# MotherBoard_PowerSupply_ebay.net
KiCad netlist of a schematic drawn in Altium Designer
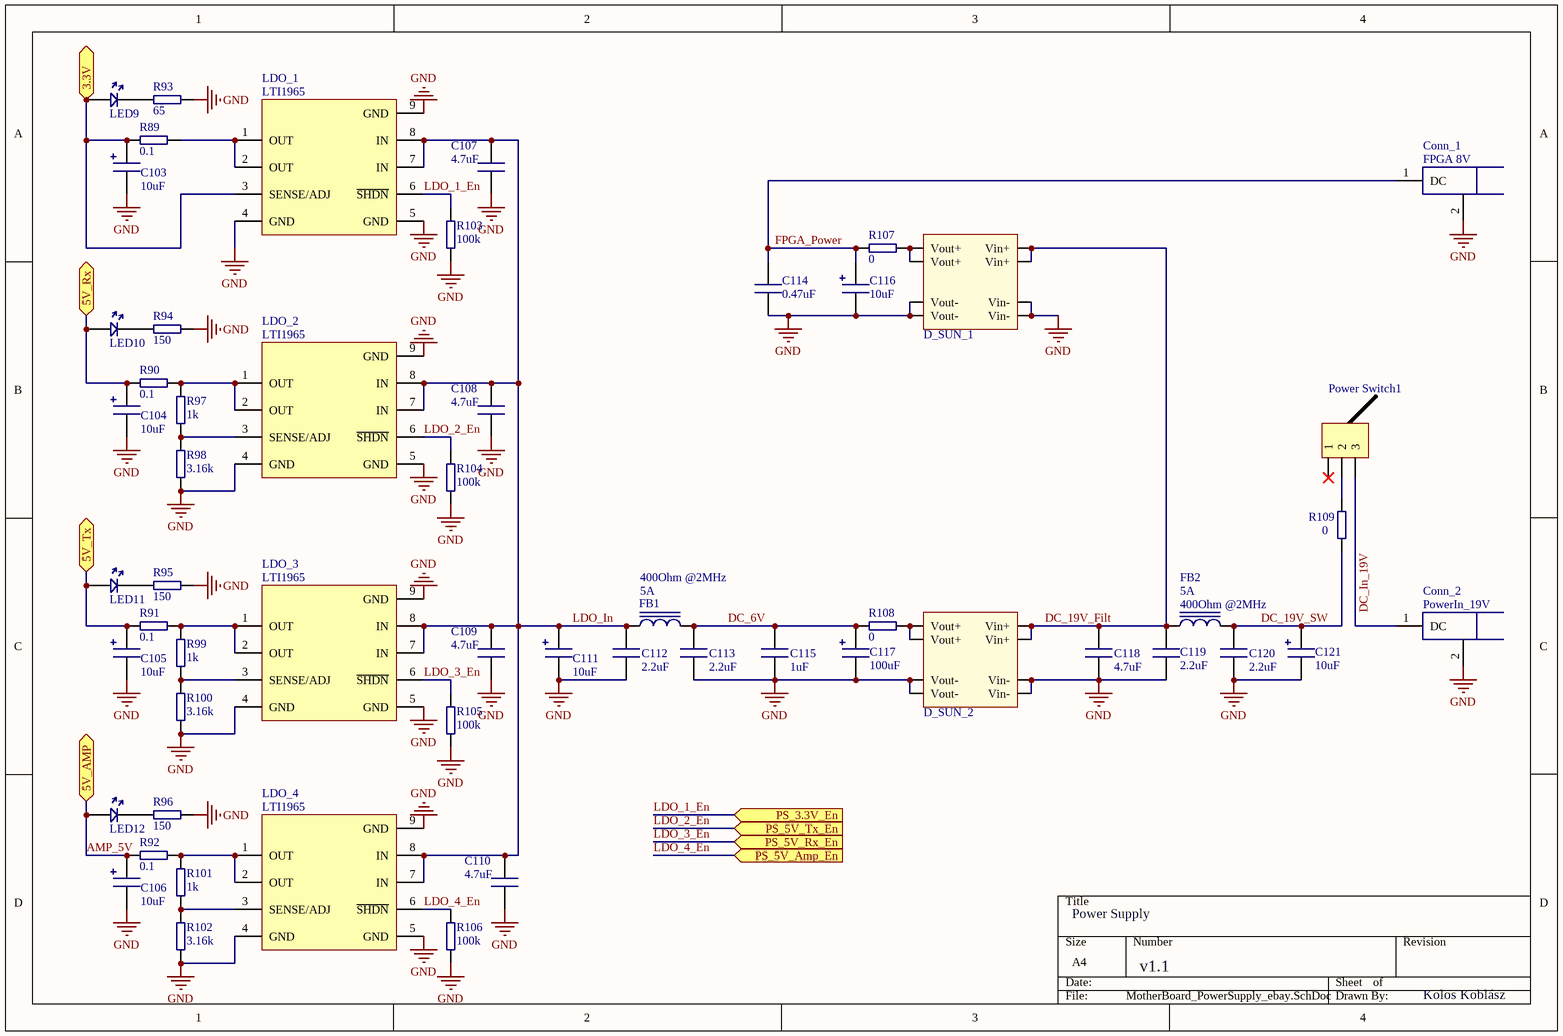
[diagram p0: MotherBoard_PowerSupply_ebay.SchDoc]

(export (version "E")
  (design (tool "Eeschema 10.0.6"))
  (components
    (comp (ref "C103")
      (value "10uF")
      (footprint "ELKO_CAP")
      (description "SMD Polarized Capacitor")
      (fields (field (name "Comment") "Cap2"))
      (libsource (lib "RadioProjectSchLib") (part "Cap2"))
    )
    (comp (ref "C104")
      (value "10uF")
      (footprint "ELKO_CAP")
      (description "SMD Polarized Capacitor")
      (fields (field (name "Comment") "Cap2"))
      (libsource (lib "RadioProjectSchLib") (part "Cap2"))
    )
    (comp (ref "C105")
      (value "10uF")
      (footprint "ELKO_CAP")
      (description "SMD Polarized Capacitor")
      (fields (field (name "Comment") "Cap2"))
      (libsource (lib "RadioProjectSchLib") (part "Cap2"))
    )
    (comp (ref "C106")
      (value "10uF")
      (footprint "ELKO_CAP")
      (description "SMD Polarized Capacitor")
      (fields (field (name "Comment") "Cap2"))
      (libsource (lib "RadioProjectSchLib") (part "Cap2"))
    )
    (comp (ref "C107")
      (value "4.7uF")
      (footprint "0805 SMD Passive")
      (description "SMD Capacitor")
      (fields (field (name "Comment") "Cap1"))
      (libsource (lib "RadioProjectSchLib") (part "Cap1"))
    )
    (comp (ref "C108")
      (value "4.7uF")
      (footprint "0805 SMD Passive")
      (description "SMD Capacitor")
      (fields (field (name "Comment") "Cap1"))
      (libsource (lib "RadioProjectSchLib") (part "Cap1"))
    )
    (comp (ref "C109")
      (value "4.7uF")
      (footprint "0805 SMD Passive")
      (description "SMD Capacitor")
      (fields (field (name "Comment") "Cap1"))
      (libsource (lib "RadioProjectSchLib") (part "Cap1"))
    )
    (comp (ref "C110")
      (value "4.7uF")
      (footprint "0805 SMD Passive")
      (description "SMD Capacitor")
      (fields (field (name "Comment") "Cap1"))
      (libsource (lib "RadioProjectSchLib") (part "Cap1"))
    )
    (comp (ref "C111")
      (value "10uF")
      (footprint "ELKO_CAP")
      (description "SMD Polarized Capacitor")
      (fields (field (name "Comment") "Cap2"))
      (libsource (lib "RadioProjectSchLib") (part "Cap2"))
    )
    (comp (ref "C112")
      (value "2.2uF")
      (footprint "0805 SMD Passive")
      (description "SMD Capacitor")
      (fields (field (name "Comment") "Cap1"))
      (libsource (lib "RadioProjectSchLib") (part "Cap1"))
    )
    (comp (ref "C113")
      (value "2.2uF")
      (footprint "0805 SMD Passive")
      (description "SMD Capacitor")
      (fields (field (name "Comment") "Cap1"))
      (libsource (lib "RadioProjectSchLib") (part "Cap1"))
    )
    (comp (ref "C114")
      (value "0.47uF")
      (footprint "0805 SMD Passive")
      (description "SMD Capacitor")
      (fields (field (name "Comment") "Cap1"))
      (libsource (lib "RadioProjectSchLib") (part "Cap1"))
    )
    (comp (ref "C115")
      (value "1uF")
      (footprint "0805 SMD Passive")
      (description "SMD Capacitor")
      (fields (field (name "Comment") "Cap1"))
      (libsource (lib "RadioProjectSchLib") (part "Cap1"))
    )
    (comp (ref "C116")
      (value "10uF")
      (footprint "ELKO_CAP")
      (description "SMD Polarized Capacitor")
      (fields (field (name "Comment") "Cap2"))
      (libsource (lib "RadioProjectSchLib") (part "Cap2"))
    )
    (comp (ref "C117")
      (value "100uF")
      (footprint "ELKO_CAP")
      (description "SMD Polarized Capacitor")
      (fields (field (name "Comment") "Cap2"))
      (libsource (lib "RadioProjectSchLib") (part "Cap2"))
    )
    (comp (ref "C118")
      (value "4.7uF")
      (footprint "0805 SMD Passive")
      (description "SMD Capacitor")
      (fields (field (name "Comment") "Cap1"))
      (libsource (lib "RadioProjectSchLib") (part "Cap1"))
    )
    (comp (ref "C119")
      (value "2.2uF")
      (footprint "0805 SMD Passive")
      (description "SMD Capacitor")
      (fields (field (name "Comment") "Cap1"))
      (libsource (lib "RadioProjectSchLib") (part "Cap1"))
    )
    (comp (ref "C120")
      (value "2.2uF")
      (footprint "0805 SMD Passive")
      (description "SMD Capacitor")
      (fields (field (name "Comment") "Cap1"))
      (libsource (lib "RadioProjectSchLib") (part "Cap1"))
    )
    (comp (ref "C121")
      (value "10uF")
      (footprint "ELKO_CAP")
      (description "SMD Polarized Capacitor")
      (fields (field (name "Comment") "Cap2"))
      (libsource (lib "RadioProjectSchLib") (part "Cap2"))
    )
    (comp (ref "Conn_1")
      (value "FPGA 8V")
      (footprint "DC_Connector")
      (description "Coaxial DC connector - female")
      (libsource (lib "RadioProjectSchLib") (part "DC_Connector"))
    )
    (comp (ref "Conn_2")
      (value "PowerIn_19V")
      (footprint "DC_Connector")
      (description "Coaxial DC connector - female")
      (libsource (lib "RadioProjectSchLib") (part "DC_Connector"))
    )
    (comp (ref "D_SUN_1")
      (value "D_SUN")
      (footprint "D_SUN")
      (description "3A DC Buck Step down Adjustable Converter Module 5-28V to 3-20V")
      (fields (field (name "MANUFACTURER") "elec modul 58"))
      (libsource (lib "RadioProjectSchLib") (part "D_SUN"))
    )
    (comp (ref "D_SUN_2")
      (value "D_SUN")
      (footprint "D_SUN")
      (description "3A DC Buck Step down Adjustable Converter Module 5-28V to 3-20V")
      (fields (field (name "MANUFACTURER") "elec modul 58"))
      (libsource (lib "RadioProjectSchLib") (part "D_SUN"))
    )
    (comp (ref "FB1")
      (value "400Ohm @2MHz")
      (footprint "FerritBead")
      (description "Ferrit Bead")
      (fields (field (name "MAXCURENT") "5A") (field (name "PARTNUMBER") "FB20022-4B-RC"))
      (libsource (lib "RadioProjectSchLib") (part "FerritBead"))
    )
    (comp (ref "FB2")
      (value "400Ohm @2MHz")
      (footprint "FerritBead")
      (description "Ferrit Bead")
      (fields (field (name "MAXCURENT") "5A") (field (name "PARTNUMBER") "FB20022-4B-RC"))
      (libsource (lib "RadioProjectSchLib") (part "FerritBead"))
    )
    (comp (ref "LDO_1")
      (value "LTI1965")
      (footprint "LT1965")
      (description "Low Dropout Linear Regulator")
      (fields (field (name "MANUFACTURER") "Analog Devices"))
      (libsource (lib "RadioProjectSchLib") (part "LTI1965"))
    )
    (comp (ref "LDO_2")
      (value "LTI1965")
      (footprint "LT1965")
      (description "Low Dropout Linear Regulator")
      (fields (field (name "MANUFACTURER") "Analog Devices"))
      (libsource (lib "RadioProjectSchLib") (part "LTI1965"))
    )
    (comp (ref "LDO_3")
      (value "LTI1965")
      (footprint "LT1965")
      (description "Low Dropout Linear Regulator")
      (fields (field (name "MANUFACTURER") "Analog Devices"))
      (libsource (lib "RadioProjectSchLib") (part "LTI1965"))
    )
    (comp (ref "LDO_4")
      (value "LTI1965")
      (footprint "LT1965")
      (description "Low Dropout Linear Regulator")
      (fields (field (name "MANUFACTURER") "Analog Devices"))
      (libsource (lib "RadioProjectSchLib") (part "LTI1965"))
    )
    (comp (ref "LED9")
      (value "LED_Green")
      (footprint "0805 SMD Passive")
      (description "Diode")
      (fields (field (name "MANUFACTURER") "LITEON") (field (name "PARTNUMBER") "LTST-C171KGKT"))
      (libsource (lib "RadioProjectSchLib") (part "LED_Green"))
    )
    (comp (ref "LED10")
      (value "LED_Green")
      (footprint "0805 SMD Passive")
      (description "Diode")
      (fields (field (name "MANUFACTURER") "LITEON") (field (name "PARTNUMBER") "LTST-C171KGKT"))
      (libsource (lib "RadioProjectSchLib") (part "LED_Green"))
    )
    (comp (ref "LED11")
      (value "LED_Green")
      (footprint "0805 SMD Passive")
      (description "Diode")
      (fields (field (name "MANUFACTURER") "LITEON") (field (name "PARTNUMBER") "LTST-C171KGKT"))
      (libsource (lib "RadioProjectSchLib") (part "LED_Green"))
    )
    (comp (ref "LED12")
      (value "LED_Green")
      (footprint "0805 SMD Passive")
      (description "Diode")
      (fields (field (name "MANUFACTURER") "LITEON") (field (name "PARTNUMBER") "LTST-C171KGKT"))
      (libsource (lib "RadioProjectSchLib") (part "LED_Green"))
    )
    (comp (ref "Power Switch1")
      (value "Switch")
      (footprint "Switch")
      (description "3 state switch")
      (libsource (lib "RadioProjectSchLib") (part "Switch"))
    )
    (comp (ref "R89")
      (value "0.1")
      (footprint "0805 SMD Passive")
      (description "SMD Resistor")
      (fields (field (name "Comment") "Resistor"))
      (libsource (lib "RadioProjectSchLib") (part "Res1"))
    )
    (comp (ref "R90")
      (value "0.1")
      (footprint "0805 SMD Passive")
      (description "SMD Resistor")
      (fields (field (name "Comment") "Resistor"))
      (libsource (lib "RadioProjectSchLib") (part "Res1"))
    )
    (comp (ref "R91")
      (value "0.1")
      (footprint "0805 SMD Passive")
      (description "SMD Resistor")
      (fields (field (name "Comment") "Resistor"))
      (libsource (lib "RadioProjectSchLib") (part "Res1"))
    )
    (comp (ref "R92")
      (value "0.1")
      (footprint "0805 SMD Passive")
      (description "SMD Resistor")
      (fields (field (name "Comment") "Resistor"))
      (libsource (lib "RadioProjectSchLib") (part "Res1"))
    )
    (comp (ref "R93")
      (value "65")
      (footprint "0805 SMD Passive")
      (description "SMD Resistor")
      (fields (field (name "Comment") "Resistor"))
      (libsource (lib "RadioProjectSchLib") (part "Res1"))
    )
    (comp (ref "R94")
      (value "150")
      (footprint "0805 SMD Passive")
      (description "SMD Resistor")
      (fields (field (name "Comment") "Resistor"))
      (libsource (lib "RadioProjectSchLib") (part "Res1"))
    )
    (comp (ref "R95")
      (value "150")
      (footprint "0805 SMD Passive")
      (description "SMD Resistor")
      (fields (field (name "Comment") "Resistor"))
      (libsource (lib "RadioProjectSchLib") (part "Res1"))
    )
    (comp (ref "R96")
      (value "150")
      (footprint "0805 SMD Passive")
      (description "SMD Resistor")
      (fields (field (name "Comment") "Resistor"))
      (libsource (lib "RadioProjectSchLib") (part "Res1"))
    )
    (comp (ref "R97")
      (value "1k")
      (footprint "0805 SMD Passive")
      (description "SMD Resistor")
      (fields (field (name "Comment") "Resistor"))
      (libsource (lib "RadioProjectSchLib") (part "Res1"))
    )
    (comp (ref "R98")
      (value "3.16k")
      (footprint "0805 SMD Passive")
      (description "SMD Resistor")
      (fields (field (name "Comment") "Resistor"))
      (libsource (lib "RadioProjectSchLib") (part "Res1"))
    )
    (comp (ref "R99")
      (value "1k")
      (footprint "0805 SMD Passive")
      (description "SMD Resistor")
      (fields (field (name "Comment") "Resistor"))
      (libsource (lib "RadioProjectSchLib") (part "Res1"))
    )
    (comp (ref "R100")
      (value "3.16k")
      (footprint "0805 SMD Passive")
      (description "SMD Resistor")
      (fields (field (name "Comment") "Resistor"))
      (libsource (lib "RadioProjectSchLib") (part "Res1"))
    )
    (comp (ref "R101")
      (value "1k")
      (footprint "0805 SMD Passive")
      (description "SMD Resistor")
      (fields (field (name "Comment") "Resistor"))
      (libsource (lib "RadioProjectSchLib") (part "Res1"))
    )
    (comp (ref "R102")
      (value "3.16k")
      (footprint "0805 SMD Passive")
      (description "SMD Resistor")
      (fields (field (name "Comment") "Resistor"))
      (libsource (lib "RadioProjectSchLib") (part "Res1"))
    )
    (comp (ref "R103")
      (value "100k")
      (footprint "0805 SMD Passive")
      (description "SMD Resistor")
      (fields (field (name "Comment") "Resistor"))
      (libsource (lib "RadioProjectSchLib") (part "Res1"))
    )
    (comp (ref "R104")
      (value "100k")
      (footprint "0805 SMD Passive")
      (description "SMD Resistor")
      (fields (field (name "Comment") "Resistor"))
      (libsource (lib "RadioProjectSchLib") (part "Res1"))
    )
    (comp (ref "R105")
      (value "100k")
      (footprint "0805 SMD Passive")
      (description "SMD Resistor")
      (fields (field (name "Comment") "Resistor"))
      (libsource (lib "RadioProjectSchLib") (part "Res1"))
    )
    (comp (ref "R106")
      (value "100k")
      (footprint "0805 SMD Passive")
      (description "SMD Resistor")
      (fields (field (name "Comment") "Resistor"))
      (libsource (lib "RadioProjectSchLib") (part "Res1"))
    )
    (comp (ref "R107")
      (value "0")
      (footprint "0805 SMD Passive")
      (description "SMD Resistor")
      (fields (field (name "Comment") "Resistor"))
      (libsource (lib "RadioProjectSchLib") (part "Res1"))
    )
    (comp (ref "R108")
      (value "0")
      (footprint "0805 SMD Passive")
      (description "SMD Resistor")
      (fields (field (name "Comment") "Resistor"))
      (libsource (lib "RadioProjectSchLib") (part "Res1"))
    )
    (comp (ref "R109")
      (value "0")
      (footprint "0805 SMD Passive")
      (description "SMD Resistor")
      (fields (field (name "Comment") "Resistor"))
      (libsource (lib "RadioProjectSchLib") (part "Res1"))
    )
  )
  (nets
    (net (code "1") (name "/3.3V") (class "Default")
      (node (ref "C103") (pin "1") (pinfunction "*_1") (pintype "passive"))
      (node (ref "LDO_1") (pin "3") (pinfunction "SENSE/ADJ_3") (pintype "passive"))
      (node (ref "LED9") (pin "2") (pinfunction "A_2") (pintype "passive"))
      (node (ref "R89") (pin "1") (pinfunction "*_1") (pintype "passive"))
    )
    (net (code "2") (name "/5V_Rx") (class "Default")
      (node (ref "C104") (pin "1") (pinfunction "*_1") (pintype "passive"))
      (node (ref "LED10") (pin "2") (pinfunction "A_2") (pintype "passive"))
      (node (ref "R90") (pin "1") (pinfunction "*_1") (pintype "passive"))
    )
    (net (code "3") (name "/5V_Tx") (class "Default")
      (node (ref "C105") (pin "1") (pinfunction "*_1") (pintype "passive"))
      (node (ref "LED11") (pin "2") (pinfunction "A_2") (pintype "passive"))
      (node (ref "R91") (pin "1") (pinfunction "*_1") (pintype "passive"))
    )
    (net (code "4") (name "/AMP_5V") (class "Default")
      (node (ref "C106") (pin "1") (pinfunction "*_1") (pintype "passive"))
      (node (ref "LED12") (pin "2") (pinfunction "A_2") (pintype "passive"))
      (node (ref "R92") (pin "1") (pinfunction "*_1") (pintype "passive"))
    )
    (net (code "5") (name "/DC_6V") (class "Default")
      (node (ref "C113") (pin "2") (pinfunction "*_2") (pintype "passive"))
      (node (ref "C115") (pin "1") (pinfunction "*_1") (pintype "passive"))
      (node (ref "C117") (pin "1") (pinfunction "*_1") (pintype "passive"))
      (node (ref "FB1") (pin "2") (pinfunction "*_2") (pintype "passive"))
      (node (ref "R108") (pin "2") (pinfunction "*_2") (pintype "passive"))
    )
    (net (code "6") (name "/DC_19V_Filt") (class "Default")
      (node (ref "C118") (pin "2") (pinfunction "*_2") (pintype "passive"))
      (node (ref "C119") (pin "2") (pinfunction "*_2") (pintype "passive"))
      (node (ref "D_SUN_1") (pin "3") (pinfunction "Vin+_3") (pintype "passive"))
      (node (ref "D_SUN_1") (pin "4") (pinfunction "Vin+_4") (pintype "passive"))
      (node (ref "D_SUN_2") (pin "3") (pinfunction "Vin+_3") (pintype "passive"))
      (node (ref "D_SUN_2") (pin "4") (pinfunction "Vin+_4") (pintype "passive"))
      (node (ref "FB2") (pin "1") (pinfunction "*_1") (pintype "passive"))
    )
    (net (code "7") (name "/DC_19V_SW") (class "Default")
      (node (ref "C120") (pin "2") (pinfunction "*_2") (pintype "passive"))
      (node (ref "C121") (pin "1") (pinfunction "*_1") (pintype "passive"))
      (node (ref "FB2") (pin "2") (pinfunction "*_2") (pintype "passive"))
      (node (ref "R109") (pin "2") (pinfunction "*_2") (pintype "passive"))
    )
    (net (code "8") (name "/DC_In_19V") (class "Default")
      (node (ref "Conn_2") (pin "1") (pinfunction "DC_1") (pintype "passive"))
      (node (ref "Power Switch1") (pin "3") (pinfunction "3_3") (pintype "passive"))
    )
    (net (code "9") (name "/FPGA_Power") (class "Default")
      (node (ref "C114") (pin "2") (pinfunction "*_2") (pintype "passive"))
      (node (ref "C116") (pin "1") (pinfunction "*_1") (pintype "passive"))
      (node (ref "Conn_1") (pin "1") (pinfunction "DC_1") (pintype "passive"))
      (node (ref "R107") (pin "2") (pinfunction "*_2") (pintype "passive"))
    )
    (net (code "10") (name "/LDO_1_En") (class "Default")
      (node (ref "LDO_1") (pin "6") (pinfunction "~{SHDN}_6") (pintype "passive"))
      (node (ref "R103") (pin "2") (pinfunction "*_2") (pintype "passive"))
    )
    (net (code "11") (name "/LDO_2_En") (class "Default")
      (node (ref "LDO_2") (pin "6") (pinfunction "~{SHDN}_6") (pintype "passive"))
      (node (ref "R104") (pin "2") (pinfunction "*_2") (pintype "passive"))
    )
    (net (code "12") (name "/LDO_3_En") (class "Default")
      (node (ref "LDO_3") (pin "6") (pinfunction "~{SHDN}_6") (pintype "passive"))
      (node (ref "R105") (pin "2") (pinfunction "*_2") (pintype "passive"))
    )
    (net (code "13") (name "/LDO_4_En") (class "Default")
      (node (ref "LDO_4") (pin "6") (pinfunction "~{SHDN}_6") (pintype "passive"))
      (node (ref "R106") (pin "2") (pinfunction "*_2") (pintype "passive"))
    )
    (net (code "14") (name "/LDO_In") (class "Default")
      (node (ref "C107") (pin "2") (pinfunction "*_2") (pintype "passive"))
      (node (ref "C108") (pin "2") (pinfunction "*_2") (pintype "passive"))
      (node (ref "C109") (pin "2") (pinfunction "*_2") (pintype "passive"))
      (node (ref "C110") (pin "2") (pinfunction "*_2") (pintype "passive"))
      (node (ref "C111") (pin "1") (pinfunction "*_1") (pintype "passive"))
      (node (ref "C112") (pin "2") (pinfunction "*_2") (pintype "passive"))
      (node (ref "FB1") (pin "1") (pinfunction "*_1") (pintype "passive"))
      (node (ref "LDO_1") (pin "7") (pinfunction "IN_7") (pintype "passive"))
      (node (ref "LDO_1") (pin "8") (pinfunction "IN_8") (pintype "passive"))
      (node (ref "LDO_2") (pin "7") (pinfunction "IN_7") (pintype "passive"))
      (node (ref "LDO_2") (pin "8") (pinfunction "IN_8") (pintype "passive"))
      (node (ref "LDO_3") (pin "7") (pinfunction "IN_7") (pintype "passive"))
      (node (ref "LDO_3") (pin "8") (pinfunction "IN_8") (pintype "passive"))
      (node (ref "LDO_4") (pin "7") (pinfunction "IN_7") (pintype "passive"))
      (node (ref "LDO_4") (pin "8") (pinfunction "IN_8") (pintype "passive"))
    )
    (net (code "15") (name "GND") (class "Default")
      (node (ref "C103") (pin "2") (pinfunction "*_2") (pintype "passive"))
      (node (ref "C104") (pin "2") (pinfunction "*_2") (pintype "passive"))
      (node (ref "C105") (pin "2") (pinfunction "*_2") (pintype "passive"))
      (node (ref "C106") (pin "2") (pinfunction "*_2") (pintype "passive"))
      (node (ref "C107") (pin "1") (pinfunction "*_1") (pintype "passive"))
      (node (ref "C108") (pin "1") (pinfunction "*_1") (pintype "passive"))
      (node (ref "C109") (pin "1") (pinfunction "*_1") (pintype "passive"))
      (node (ref "C110") (pin "1") (pinfunction "*_1") (pintype "passive"))
      (node (ref "C111") (pin "2") (pinfunction "*_2") (pintype "passive"))
      (node (ref "C112") (pin "1") (pinfunction "*_1") (pintype "passive"))
      (node (ref "C113") (pin "1") (pinfunction "*_1") (pintype "passive"))
      (node (ref "C114") (pin "1") (pinfunction "*_1") (pintype "passive"))
      (node (ref "C115") (pin "2") (pinfunction "*_2") (pintype "passive"))
      (node (ref "C116") (pin "2") (pinfunction "*_2") (pintype "passive"))
      (node (ref "C117") (pin "2") (pinfunction "*_2") (pintype "passive"))
      (node (ref "C118") (pin "1") (pinfunction "*_1") (pintype "passive"))
      (node (ref "C119") (pin "1") (pinfunction "*_1") (pintype "passive"))
      (node (ref "C120") (pin "1") (pinfunction "*_1") (pintype "passive"))
      (node (ref "C121") (pin "2") (pinfunction "*_2") (pintype "passive"))
      (node (ref "Conn_1") (pin "2") (pinfunction "GND_2") (pintype "passive"))
      (node (ref "Conn_2") (pin "2") (pinfunction "GND_2") (pintype "passive"))
      (node (ref "D_SUN_1") (pin "1") (pinfunction "Vin-_1") (pintype "passive"))
      (node (ref "D_SUN_1") (pin "2") (pinfunction "Vin-_2") (pintype "passive"))
      (node (ref "D_SUN_1") (pin "7") (pinfunction "Vout-_7") (pintype "passive"))
      (node (ref "D_SUN_1") (pin "8") (pinfunction "Vout-_8") (pintype "passive"))
      (node (ref "D_SUN_2") (pin "1") (pinfunction "Vin-_1") (pintype "passive"))
      (node (ref "D_SUN_2") (pin "2") (pinfunction "Vin-_2") (pintype "passive"))
      (node (ref "D_SUN_2") (pin "7") (pinfunction "Vout-_7") (pintype "passive"))
      (node (ref "D_SUN_2") (pin "8") (pinfunction "Vout-_8") (pintype "passive"))
      (node (ref "LDO_1") (pin "4") (pinfunction "GND_4") (pintype "passive"))
      (node (ref "LDO_1") (pin "5") (pinfunction "GND_5") (pintype "passive"))
      (node (ref "LDO_1") (pin "9") (pinfunction "GND_9") (pintype "passive"))
      (node (ref "LDO_2") (pin "4") (pinfunction "GND_4") (pintype "passive"))
      (node (ref "LDO_2") (pin "5") (pinfunction "GND_5") (pintype "passive"))
      (node (ref "LDO_2") (pin "9") (pinfunction "GND_9") (pintype "passive"))
      (node (ref "LDO_3") (pin "4") (pinfunction "GND_4") (pintype "passive"))
      (node (ref "LDO_3") (pin "5") (pinfunction "GND_5") (pintype "passive"))
      (node (ref "LDO_3") (pin "9") (pinfunction "GND_9") (pintype "passive"))
      (node (ref "LDO_4") (pin "4") (pinfunction "GND_4") (pintype "passive"))
      (node (ref "LDO_4") (pin "5") (pinfunction "GND_5") (pintype "passive"))
      (node (ref "LDO_4") (pin "9") (pinfunction "GND_9") (pintype "passive"))
      (node (ref "R100") (pin "1") (pinfunction "*_1") (pintype "passive"))
      (node (ref "R102") (pin "1") (pinfunction "*_1") (pintype "passive"))
      (node (ref "R103") (pin "1") (pinfunction "*_1") (pintype "passive"))
      (node (ref "R104") (pin "1") (pinfunction "*_1") (pintype "passive"))
      (node (ref "R105") (pin "1") (pinfunction "*_1") (pintype "passive"))
      (node (ref "R106") (pin "1") (pinfunction "*_1") (pintype "passive"))
      (node (ref "R93") (pin "2") (pinfunction "*_2") (pintype "passive"))
      (node (ref "R94") (pin "2") (pinfunction "*_2") (pintype "passive"))
      (node (ref "R95") (pin "2") (pinfunction "*_2") (pintype "passive"))
      (node (ref "R96") (pin "2") (pinfunction "*_2") (pintype "passive"))
      (node (ref "R98") (pin "1") (pinfunction "*_1") (pintype "passive"))
    )
    (net (code "16") (name "Net-(D_SUN_1-Vout+-Pad5)") (class "Default")
      (node (ref "D_SUN_1") (pin "5") (pinfunction "Vout+_5") (pintype "passive"))
      (node (ref "D_SUN_1") (pin "6") (pinfunction "Vout+_6") (pintype "passive"))
      (node (ref "R107") (pin "1") (pinfunction "*_1") (pintype "passive"))
    )
    (net (code "17") (name "Net-(D_SUN_2-Vout+-Pad5)") (class "Default")
      (node (ref "D_SUN_2") (pin "5") (pinfunction "Vout+_5") (pintype "passive"))
      (node (ref "D_SUN_2") (pin "6") (pinfunction "Vout+_6") (pintype "passive"))
      (node (ref "R108") (pin "1") (pinfunction "*_1") (pintype "passive"))
    )
    (net (code "18") (name "Net-(LDO_1-OUT-Pad1)") (class "Default")
      (node (ref "LDO_1") (pin "1") (pinfunction "OUT_1") (pintype "passive"))
      (node (ref "LDO_1") (pin "2") (pinfunction "OUT_2") (pintype "passive"))
      (node (ref "R89") (pin "2") (pinfunction "*_2") (pintype "passive"))
    )
    (net (code "19") (name "Net-(LDO_2-OUT-Pad1)") (class "Default")
      (node (ref "LDO_2") (pin "1") (pinfunction "OUT_1") (pintype "passive"))
      (node (ref "LDO_2") (pin "2") (pinfunction "OUT_2") (pintype "passive"))
      (node (ref "R90") (pin "2") (pinfunction "*_2") (pintype "passive"))
      (node (ref "R97") (pin "2") (pinfunction "*_2") (pintype "passive"))
    )
    (net (code "20") (name "Net-(LDO_2-SENSE{slash}ADJ)") (class "Default")
      (node (ref "LDO_2") (pin "3") (pinfunction "SENSE/ADJ_3") (pintype "passive"))
      (node (ref "R97") (pin "1") (pinfunction "*_1") (pintype "passive"))
      (node (ref "R98") (pin "2") (pinfunction "*_2") (pintype "passive"))
    )
    (net (code "21") (name "Net-(LDO_3-OUT-Pad1)") (class "Default")
      (node (ref "LDO_3") (pin "1") (pinfunction "OUT_1") (pintype "passive"))
      (node (ref "LDO_3") (pin "2") (pinfunction "OUT_2") (pintype "passive"))
      (node (ref "R91") (pin "2") (pinfunction "*_2") (pintype "passive"))
      (node (ref "R99") (pin "2") (pinfunction "*_2") (pintype "passive"))
    )
    (net (code "22") (name "Net-(LDO_3-SENSE{slash}ADJ)") (class "Default")
      (node (ref "LDO_3") (pin "3") (pinfunction "SENSE/ADJ_3") (pintype "passive"))
      (node (ref "R100") (pin "2") (pinfunction "*_2") (pintype "passive"))
      (node (ref "R99") (pin "1") (pinfunction "*_1") (pintype "passive"))
    )
    (net (code "23") (name "Net-(LDO_4-OUT-Pad1)") (class "Default")
      (node (ref "LDO_4") (pin "1") (pinfunction "OUT_1") (pintype "passive"))
      (node (ref "LDO_4") (pin "2") (pinfunction "OUT_2") (pintype "passive"))
      (node (ref "R101") (pin "2") (pinfunction "*_2") (pintype "passive"))
      (node (ref "R92") (pin "2") (pinfunction "*_2") (pintype "passive"))
    )
    (net (code "24") (name "Net-(LDO_4-SENSE{slash}ADJ)") (class "Default")
      (node (ref "LDO_4") (pin "3") (pinfunction "SENSE/ADJ_3") (pintype "passive"))
      (node (ref "R101") (pin "1") (pinfunction "*_1") (pintype "passive"))
      (node (ref "R102") (pin "2") (pinfunction "*_2") (pintype "passive"))
    )
    (net (code "25") (name "Net-(LED9-K)") (class "Default")
      (node (ref "LED9") (pin "1") (pinfunction "K_1") (pintype "passive"))
      (node (ref "R93") (pin "1") (pinfunction "*_1") (pintype "passive"))
    )
    (net (code "26") (name "Net-(LED10-K)") (class "Default")
      (node (ref "LED10") (pin "1") (pinfunction "K_1") (pintype "passive"))
      (node (ref "R94") (pin "1") (pinfunction "*_1") (pintype "passive"))
    )
    (net (code "27") (name "Net-(LED11-K)") (class "Default")
      (node (ref "LED11") (pin "1") (pinfunction "K_1") (pintype "passive"))
      (node (ref "R95") (pin "1") (pinfunction "*_1") (pintype "passive"))
    )
    (net (code "28") (name "Net-(LED12-K)") (class "Default")
      (node (ref "LED12") (pin "1") (pinfunction "K_1") (pintype "passive"))
      (node (ref "R96") (pin "1") (pinfunction "*_1") (pintype "passive"))
    )
    (net (code "29") (name "Net-(Power Switch1-Pad2)") (class "Default")
      (node (ref "Power Switch1") (pin "2") (pinfunction "2_2") (pintype "passive"))
      (node (ref "R109") (pin "1") (pinfunction "*_1") (pintype "passive"))
    )
    (net (code "30") (name "unconnected-(Power Switch1-Pad1)") (class "Default")
      (node (ref "Power Switch1") (pin "1") (pinfunction "1_1") (pintype "passive+no_connect"))
    )
  )
)
